# breakout-lrtb-g6tg_full.net
KiCad netlist of a schematic drawn in EAGLE
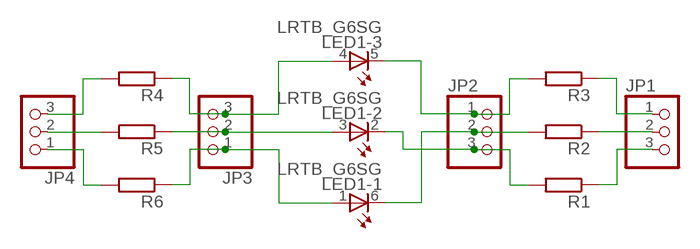
[diagram p0: schematic, sheet 1]

(export (version "E")
  (design (tool "Eeschema 10.0.6"))
  (components
    (comp (ref "JP1")
      (value "PINHD-1X3")
      (footprint "eagle-import:1X03")
      (libsource (lib "eagle-import") (part "PINHD-1X3"))
    )
    (comp (ref "JP2")
      (value "PINHD-1X3")
      (footprint "eagle-import:1X03")
      (libsource (lib "eagle-import") (part "PINHD-1X3"))
    )
    (comp (ref "JP3")
      (value "PINHD-1X3")
      (footprint "eagle-import:1X03")
      (libsource (lib "eagle-import") (part "PINHD-1X3"))
    )
    (comp (ref "JP4")
      (value "PINHD-1X3")
      (footprint "eagle-import:1X03")
      (libsource (lib "eagle-import") (part "PINHD-1X3"))
    )
    (comp (ref "LED1")
      (value "LRTB_G6SG")
      (footprint "eagle-import:LRTB_G6SG")
      (libsource (lib "eagle-import") (part "LRTB_G6SG"))
    )
    (comp (ref "R1")
      (value "R-EU_R0805")
      (footprint "eagle-import:R0805")
      (libsource (lib "eagle-import") (part "R-EU_R0805"))
    )
    (comp (ref "R2")
      (value "R-EU_R0805")
      (footprint "eagle-import:R0805")
      (libsource (lib "eagle-import") (part "R-EU_R0805"))
    )
    (comp (ref "R3")
      (value "R-EU_R0805")
      (footprint "eagle-import:R0805")
      (libsource (lib "eagle-import") (part "R-EU_R0805"))
    )
    (comp (ref "R4")
      (value "R-EU_R0805")
      (footprint "eagle-import:R0805")
      (libsource (lib "eagle-import") (part "R-EU_R0805"))
    )
    (comp (ref "R5")
      (value "R-EU_R0805")
      (footprint "eagle-import:R0805")
      (libsource (lib "eagle-import") (part "R-EU_R0805"))
    )
    (comp (ref "R6")
      (value "R-EU_R0805")
      (footprint "eagle-import:R0805")
      (libsource (lib "eagle-import") (part "R-EU_R0805"))
    )
  )
  (nets
    (net (code "1") (name "Net-(JP1-Pad1)") (class "Default")
      (node (ref "JP1") (pin "1") (pinfunction "1_1") (pintype "passive"))
      (node (ref "R3") (pin "1") (pinfunction "1_1") (pintype "passive"))
    )
    (net (code "2") (name "Net-(JP1-Pad2)") (class "Default")
      (node (ref "JP1") (pin "2") (pinfunction "2_2") (pintype "passive"))
      (node (ref "R2") (pin "1") (pinfunction "1_1") (pintype "passive"))
    )
    (net (code "3") (name "Net-(JP1-Pad3)") (class "Default")
      (node (ref "JP1") (pin "3") (pinfunction "3_3") (pintype "passive"))
      (node (ref "R1") (pin "1") (pinfunction "1_1") (pintype "passive"))
    )
    (net (code "4") (name "Net-(JP4-Pad1)") (class "Default")
      (node (ref "JP4") (pin "1") (pinfunction "1_1") (pintype "passive"))
      (node (ref "R6") (pin "2") (pinfunction "2_2") (pintype "passive"))
    )
    (net (code "5") (name "Net-(JP4-Pad2)") (class "Default")
      (node (ref "JP4") (pin "2") (pinfunction "2_2") (pintype "passive"))
      (node (ref "R5") (pin "2") (pinfunction "2_2") (pintype "passive"))
    )
    (net (code "6") (name "Net-(JP4-Pad3)") (class "Default")
      (node (ref "JP4") (pin "3") (pinfunction "3_3") (pintype "passive"))
      (node (ref "R4") (pin "2") (pinfunction "2_2") (pintype "passive"))
    )
    (net (code "7") (name "Net-(LED1A-A)") (class "Default")
      (node (ref "JP3") (pin "1") (pinfunction "1_1") (pintype "passive"))
      (node (ref "LED1") (pin "1") (pinfunction "A_1") (pintype "passive"))
      (node (ref "R6") (pin "1") (pinfunction "1_1") (pintype "passive"))
    )
    (net (code "8") (name "Net-(LED1A-C)") (class "Default")
      (node (ref "JP2") (pin "2") (pinfunction "2_2") (pintype "passive"))
      (node (ref "LED1") (pin "6") (pinfunction "C_6") (pintype "passive"))
      (node (ref "R2") (pin "2") (pinfunction "2_2") (pintype "passive"))
    )
    (net (code "9") (name "Net-(LED1B-A)") (class "Default")
      (node (ref "JP3") (pin "2") (pinfunction "2_2") (pintype "passive"))
      (node (ref "LED1") (pin "3") (pinfunction "A_3") (pintype "passive"))
      (node (ref "R5") (pin "1") (pinfunction "1_1") (pintype "passive"))
    )
    (net (code "10") (name "Net-(LED1B-C)") (class "Default")
      (node (ref "JP2") (pin "3") (pinfunction "3_3") (pintype "passive"))
      (node (ref "LED1") (pin "2") (pinfunction "C_2") (pintype "passive"))
      (node (ref "R1") (pin "2") (pinfunction "2_2") (pintype "passive"))
    )
    (net (code "11") (name "Net-(LED1C-A)") (class "Default")
      (node (ref "JP3") (pin "3") (pinfunction "3_3") (pintype "passive"))
      (node (ref "LED1") (pin "4") (pinfunction "A_4") (pintype "passive"))
      (node (ref "R4") (pin "1") (pinfunction "1_1") (pintype "passive"))
    )
    (net (code "12") (name "Net-(LED1C-C)") (class "Default")
      (node (ref "JP2") (pin "1") (pinfunction "1_1") (pintype "passive"))
      (node (ref "LED1") (pin "5") (pinfunction "C_5") (pintype "passive"))
      (node (ref "R3") (pin "2") (pinfunction "2_2") (pintype "passive"))
    )
  )
)
